# RPi_Carrier.net
KiCad netlist of a schematic drawn in Altium Designer
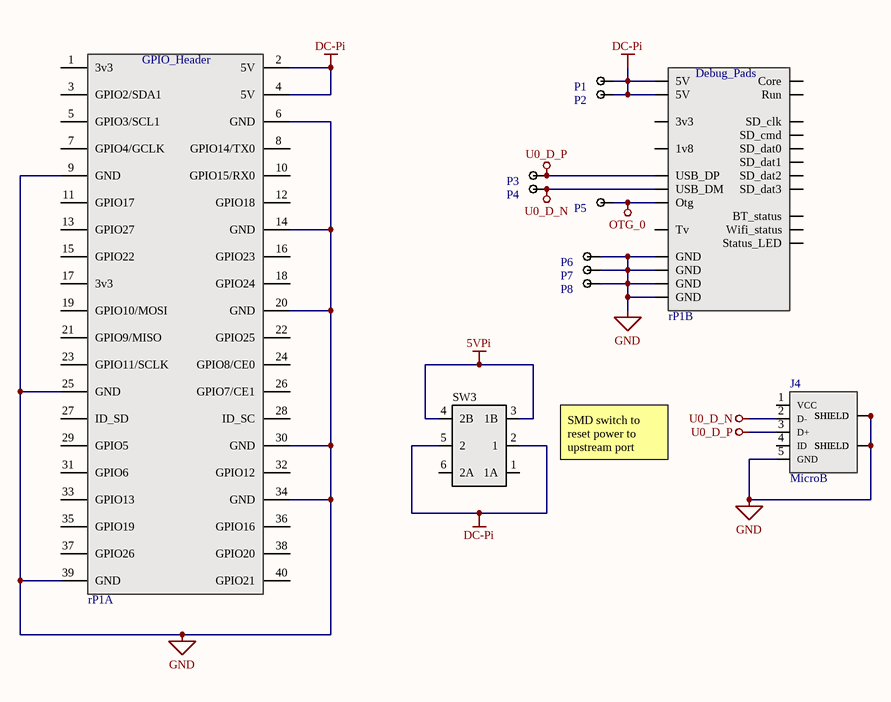
[diagram p0: RPi_Carrier.SchDoc]

(export (version "E")
  (design (tool "Eeschema 10.0.6"))
  (components
    (comp (ref "J4")
      (value "MicroB")
      (footprint "10118194-0001LF")
      (description "Micro USB, Input Output Connectors, B TYPE RECEPTACLE with flange")
      (fields (field (name "MF") "Amphenol ICC") (field (name "MP") "10118194-0001LF"))
      (libsource (lib "Connectors") (part "10118194-0001LF"))
    )
    (comp (ref "P1")
      (value "MillMax Pogo")
      (footprint "0914-1-15-20-77-14-11-0")
      (description "MillMax Pogo Pins/Probes")
      (libsource (lib "Connectors") (part "GenericPogo"))
    )
    (comp (ref "P2")
      (value "MillMax Pogo")
      (footprint "0914-1-15-20-77-14-11-0")
      (description "MillMax Pogo Pins/Probes")
      (libsource (lib "Connectors") (part "GenericPogo"))
    )
    (comp (ref "P3")
      (value "MillMax Pogo")
      (footprint "0914-1-15-20-77-14-11-0")
      (description "MillMax Pogo Pins/Probes")
      (libsource (lib "Connectors") (part "GenericPogo"))
    )
    (comp (ref "P4")
      (value "MillMax Pogo")
      (footprint "0914-1-15-20-77-14-11-0")
      (description "MillMax Pogo Pins/Probes")
      (libsource (lib "Connectors") (part "GenericPogo"))
    )
    (comp (ref "P5")
      (value "MillMax Pogo")
      (footprint "0914-1-15-20-77-14-11-0")
      (description "MillMax Pogo Pins/Probes")
      (libsource (lib "Connectors") (part "GenericPogo"))
    )
    (comp (ref "P6")
      (value "MillMax Pogo")
      (footprint "0914-1-15-20-77-14-11-0")
      (description "MillMax Pogo Pins/Probes")
      (libsource (lib "Connectors") (part "GenericPogo"))
    )
    (comp (ref "P7")
      (value "MillMax Pogo")
      (footprint "0914-1-15-20-77-14-11-0")
      (description "MillMax Pogo Pins/Probes")
      (libsource (lib "Connectors") (part "GenericPogo"))
    )
    (comp (ref "P8")
      (value "MillMax Pogo")
      (footprint "0914-1-15-20-77-14-11-0")
      (description "MillMax Pogo Pins/Probes")
      (libsource (lib "Connectors") (part "GenericPogo"))
    )
    (comp (ref "rP1")
      (value "rPi Zero Carrier")
      (footprint "rPiZero")
      (description "Raspberry Pi Zero/W/2W\r\nHeader, debug-pads, & mounting")
      (libsource (lib "Misc ICs") (part "RP-Zero"))
    )
    (comp (ref "SW3")
      (value "~")
      (footprint "SMD-DPDT-SW")
      (description "Brick nogging DPDT Black SMD Slide Switch")
      (libsource (lib "Switches") (part "MS-22D17-G2"))
    )
  )
  (nets
    (net (code "1") (name "5VPi") (class "Default")
      (node (ref "SW3") (pin "3") (pinfunction "1B_3") (pintype "passive"))
      (node (ref "SW3") (pin "4") (pinfunction "2B_4") (pintype "passive"))
    )
    (net (code "2") (name "DC-Pi") (class "Default")
      (node (ref "P1") (pin "1") (pinfunction "1_1") (pintype "passive"))
      (node (ref "P2") (pin "1") (pinfunction "1_1") (pintype "passive"))
      (node (ref "SW3") (pin "2") (pinfunction "1_2") (pintype "passive"))
      (node (ref "SW3") (pin "5") (pinfunction "2_5") (pintype "passive"))
      (node (ref "rP1") (pin "2") (pinfunction "5V_2") (pintype "passive"))
      (node (ref "rP1") (pin "4") (pinfunction "5V_4") (pintype "passive"))
      (node (ref "rP1") (pin "5V1") (pinfunction "5V_5V1") (pintype "passive"))
      (node (ref "rP1") (pin "5V2") (pinfunction "5V_5V2") (pintype "passive"))
    )
    (net (code "3") (name "GND") (class "Default")
      (node (ref "J4") (pin "5") (pinfunction "GND_5") (pintype "power_in"))
      (node (ref "J4") (pin "SH1") (pinfunction "SHIELD_SH1") (pintype "passive"))
      (node (ref "J4") (pin "SH2") (pinfunction "SHIELD_SH2") (pintype "passive"))
      (node (ref "J4") (pin "SH3") (pinfunction "SHIELD_SH3") (pintype "passive"))
      (node (ref "J4") (pin "SH4") (pinfunction "SHIELD_SH4") (pintype "passive"))
      (node (ref "J4") (pin "SH5") (pinfunction "SHIELD_SH5") (pintype "passive"))
      (node (ref "J4") (pin "SH6") (pinfunction "SHIELD_SH6") (pintype "passive"))
      (node (ref "P6") (pin "1") (pinfunction "1_1") (pintype "passive"))
      (node (ref "P7") (pin "1") (pinfunction "1_1") (pintype "passive"))
      (node (ref "P8") (pin "1") (pinfunction "1_1") (pintype "passive"))
      (node (ref "rP1") (pin "14") (pinfunction "GND_14") (pintype "passive"))
      (node (ref "rP1") (pin "20") (pinfunction "GND_20") (pintype "passive"))
      (node (ref "rP1") (pin "25") (pinfunction "GND_25") (pintype "passive"))
      (node (ref "rP1") (pin "30") (pinfunction "GND_30") (pintype "passive"))
      (node (ref "rP1") (pin "34") (pinfunction "GND_34") (pintype "passive"))
      (node (ref "rP1") (pin "39") (pinfunction "GND_39") (pintype "passive"))
      (node (ref "rP1") (pin "6") (pinfunction "GND_6") (pintype "passive"))
      (node (ref "rP1") (pin "9") (pinfunction "GND_9") (pintype "passive"))
      (node (ref "rP1") (pin "G1") (pinfunction "GND_G1") (pintype "passive"))
      (node (ref "rP1") (pin "G2") (pinfunction "GND_G2") (pintype "passive"))
      (node (ref "rP1") (pin "G3") (pinfunction "GND_G3") (pintype "passive"))
      (node (ref "rP1") (pin "G4") (pinfunction "GND_G4") (pintype "passive"))
    )
    (net (code "4") (name "OTG_0") (class "Default")
      (node (ref "P5") (pin "1") (pinfunction "1_1") (pintype "passive"))
      (node (ref "rP1") (pin "OTG") (pinfunction "Otg_OTG") (pintype "passive"))
    )
    (net (code "5") (name "U0_D_N") (class "Default")
      (node (ref "J4") (pin "2") (pinfunction "D-_2") (pintype "bidirectional"))
      (node (ref "P4") (pin "1") (pinfunction "1_1") (pintype "passive"))
      (node (ref "rP1") (pin "USB_DM") (pinfunction "USB_DM_USB_DM") (pintype "passive"))
    )
    (net (code "6") (name "U0_D_P") (class "Default")
      (node (ref "J4") (pin "3") (pinfunction "D+_3") (pintype "bidirectional"))
      (node (ref "P3") (pin "1") (pinfunction "1_1") (pintype "passive"))
      (node (ref "rP1") (pin "USB_DP") (pinfunction "USB_DP_USB_DP") (pintype "passive"))
    )
    (net (code "7") (name "unconnected-(J4-ID-Pad4)") (class "Default")
      (node (ref "J4") (pin "4") (pinfunction "ID_4") (pintype "bidirectional"))
    )
    (net (code "8") (name "unconnected-(J4-VCC-Pad1)") (class "Default")
      (node (ref "J4") (pin "1") (pinfunction "VCC_1") (pintype "power_in"))
    )
    (net (code "9") (name "unconnected-(SW3-1A-Pad1)") (class "Default")
      (node (ref "SW3") (pin "1") (pinfunction "1A_1") (pintype "passive"))
    )
    (net (code "10") (name "unconnected-(SW3-2A-Pad6)") (class "Default")
      (node (ref "SW3") (pin "6") (pinfunction "2A_6") (pintype "passive"))
    )
    (net (code "11") (name "unconnected-(rP1A-3v3-Pad1)") (class "Default")
      (node (ref "rP1") (pin "1") (pinfunction "3v3_1") (pintype "passive"))
    )
    (net (code "12") (name "unconnected-(rP1A-3v3-Pad17)") (class "Default")
      (node (ref "rP1") (pin "17") (pinfunction "3v3_17") (pintype "passive"))
    )
    (net (code "13") (name "unconnected-(rP1A-GPIO2{slash}SDA1-Pad3)") (class "Default")
      (node (ref "rP1") (pin "3") (pinfunction "GPIO2/SDA1_3") (pintype "passive"))
    )
    (net (code "14") (name "unconnected-(rP1A-GPIO3{slash}SCL1-Pad5)") (class "Default")
      (node (ref "rP1") (pin "5") (pinfunction "GPIO3/SCL1_5") (pintype "passive"))
    )
    (net (code "15") (name "unconnected-(rP1A-GPIO4{slash}GCLK-Pad7)") (class "Default")
      (node (ref "rP1") (pin "7") (pinfunction "GPIO4/GCLK_7") (pintype "passive"))
    )
    (net (code "16") (name "unconnected-(rP1A-GPIO5-Pad29)") (class "Default")
      (node (ref "rP1") (pin "29") (pinfunction "GPIO5_29") (pintype "passive"))
    )
    (net (code "17") (name "unconnected-(rP1A-GPIO6-Pad31)") (class "Default")
      (node (ref "rP1") (pin "31") (pinfunction "GPIO6_31") (pintype "passive"))
    )
    (net (code "18") (name "unconnected-(rP1A-GPIO7{slash}CE1-Pad26)") (class "Default")
      (node (ref "rP1") (pin "26") (pinfunction "GPIO7/CE1_26") (pintype "passive"))
    )
    (net (code "19") (name "unconnected-(rP1A-GPIO8{slash}CE0-Pad24)") (class "Default")
      (node (ref "rP1") (pin "24") (pinfunction "GPIO8/CE0_24") (pintype "passive"))
    )
    (net (code "20") (name "unconnected-(rP1A-GPIO9{slash}MISO-Pad21)") (class "Default")
      (node (ref "rP1") (pin "21") (pinfunction "GPIO9/MISO_21") (pintype "passive"))
    )
    (net (code "21") (name "unconnected-(rP1A-GPIO10{slash}MOSI-Pad19)") (class "Default")
      (node (ref "rP1") (pin "19") (pinfunction "GPIO10/MOSI_19") (pintype "passive"))
    )
    (net (code "22") (name "unconnected-(rP1A-GPIO11{slash}SCLK-Pad23)") (class "Default")
      (node (ref "rP1") (pin "23") (pinfunction "GPIO11/SCLK_23") (pintype "passive"))
    )
    (net (code "23") (name "unconnected-(rP1A-GPIO12-Pad32)") (class "Default")
      (node (ref "rP1") (pin "32") (pinfunction "GPIO12_32") (pintype "passive"))
    )
    (net (code "24") (name "unconnected-(rP1A-GPIO13-Pad33)") (class "Default")
      (node (ref "rP1") (pin "33") (pinfunction "GPIO13_33") (pintype "passive"))
    )
    (net (code "25") (name "unconnected-(rP1A-GPIO14{slash}TX0-Pad8)") (class "Default")
      (node (ref "rP1") (pin "8") (pinfunction "GPIO14/TX0_8") (pintype "passive"))
    )
    (net (code "26") (name "unconnected-(rP1A-GPIO15{slash}RX0-Pad10)") (class "Default")
      (node (ref "rP1") (pin "10") (pinfunction "GPIO15/RX0_10") (pintype "passive"))
    )
    (net (code "27") (name "unconnected-(rP1A-GPIO16-Pad36)") (class "Default")
      (node (ref "rP1") (pin "36") (pinfunction "GPIO16_36") (pintype "passive"))
    )
    (net (code "28") (name "unconnected-(rP1A-GPIO17-Pad11)") (class "Default")
      (node (ref "rP1") (pin "11") (pinfunction "GPIO17_11") (pintype "passive"))
    )
    (net (code "29") (name "unconnected-(rP1A-GPIO18-Pad12)") (class "Default")
      (node (ref "rP1") (pin "12") (pinfunction "GPIO18_12") (pintype "passive"))
    )
    (net (code "30") (name "unconnected-(rP1A-GPIO19-Pad35)") (class "Default")
      (node (ref "rP1") (pin "35") (pinfunction "GPIO19_35") (pintype "passive"))
    )
    (net (code "31") (name "unconnected-(rP1A-GPIO20-Pad38)") (class "Default")
      (node (ref "rP1") (pin "38") (pinfunction "GPIO20_38") (pintype "passive"))
    )
    (net (code "32") (name "unconnected-(rP1A-GPIO21-Pad40)") (class "Default")
      (node (ref "rP1") (pin "40") (pinfunction "GPIO21_40") (pintype "passive"))
    )
    (net (code "33") (name "unconnected-(rP1A-GPIO22-Pad15)") (class "Default")
      (node (ref "rP1") (pin "15") (pinfunction "GPIO22_15") (pintype "passive"))
    )
    (net (code "34") (name "unconnected-(rP1A-GPIO23-Pad16)") (class "Default")
      (node (ref "rP1") (pin "16") (pinfunction "GPIO23_16") (pintype "passive"))
    )
    (net (code "35") (name "unconnected-(rP1A-GPIO24-Pad18)") (class "Default")
      (node (ref "rP1") (pin "18") (pinfunction "GPIO24_18") (pintype "passive"))
    )
    (net (code "36") (name "unconnected-(rP1A-GPIO25-Pad22)") (class "Default")
      (node (ref "rP1") (pin "22") (pinfunction "GPIO25_22") (pintype "passive"))
    )
    (net (code "37") (name "unconnected-(rP1A-GPIO26-Pad37)") (class "Default")
      (node (ref "rP1") (pin "37") (pinfunction "GPIO26_37") (pintype "passive"))
    )
    (net (code "38") (name "unconnected-(rP1A-GPIO27-Pad13)") (class "Default")
      (node (ref "rP1") (pin "13") (pinfunction "GPIO27_13") (pintype "passive"))
    )
    (net (code "39") (name "unconnected-(rP1A-ID_SC-Pad28)") (class "Default")
      (node (ref "rP1") (pin "28") (pinfunction "ID_SC_28") (pintype "passive"))
    )
    (net (code "40") (name "unconnected-(rP1A-ID_SD-Pad27)") (class "Default")
      (node (ref "rP1") (pin "27") (pinfunction "ID_SD_27") (pintype "passive"))
    )
    (net (code "41") (name "unconnected-(rP1B-1v8-Pad1V8)") (class "Default")
      (node (ref "rP1") (pin "1V8") (pinfunction "1v8_1V8") (pintype "passive"))
    )
    (net (code "42") (name "unconnected-(rP1B-3v3-Pad3V3)") (class "Default")
      (node (ref "rP1") (pin "3V3") (pinfunction "3v3_3V3") (pintype "passive"))
    )
    (net (code "43") (name "unconnected-(rP1B-BT_status-PadBT_ON)") (class "Default")
      (node (ref "rP1") (pin "BT_ON") (pinfunction "BT_status_BT_ON") (pintype "passive"))
    )
    (net (code "44") (name "unconnected-(rP1B-Core-PadCORE)") (class "Default")
      (node (ref "rP1") (pin "CORE") (pinfunction "Core_CORE") (pintype "passive"))
    )
    (net (code "45") (name "unconnected-(rP1B-Run-PadRUN)") (class "Default")
      (node (ref "rP1") (pin "RUN") (pinfunction "Run_RUN") (pintype "passive"))
    )
    (net (code "46") (name "unconnected-(rP1B-SD_clk-PadSD_CLK)") (class "Default")
      (node (ref "rP1") (pin "SD_CLK") (pinfunction "SD_clk_SD_CLK") (pintype "passive"))
    )
    (net (code "47") (name "unconnected-(rP1B-SD_cmd-PadSD_CMD)") (class "Default")
      (node (ref "rP1") (pin "SD_CMD") (pinfunction "SD_cmd_SD_CMD") (pintype "passive"))
    )
    (net (code "48") (name "unconnected-(rP1B-SD_dat0-PadSD_DAT0)") (class "Default")
      (node (ref "rP1") (pin "SD_DAT0") (pinfunction "SD_dat0_SD_DAT0") (pintype "passive"))
    )
    (net (code "49") (name "unconnected-(rP1B-SD_dat1-PadSD_DAT1)") (class "Default")
      (node (ref "rP1") (pin "SD_DAT1") (pinfunction "SD_dat1_SD_DAT1") (pintype "passive"))
    )
    (net (code "50") (name "unconnected-(rP1B-SD_dat2-PadSD_DAT2)") (class "Default")
      (node (ref "rP1") (pin "SD_DAT2") (pinfunction "SD_dat2_SD_DAT2") (pintype "passive"))
    )
    (net (code "51") (name "unconnected-(rP1B-SD_dat3-PadSD_DAT3)") (class "Default")
      (node (ref "rP1") (pin "SD_DAT3") (pinfunction "SD_dat3_SD_DAT3") (pintype "passive"))
    )
    (net (code "52") (name "unconnected-(rP1B-Status_LED-PadSTATUS)") (class "Default")
      (node (ref "rP1") (pin "STATUS") (pinfunction "Status_LED_STATUS") (pintype "passive"))
    )
    (net (code "53") (name "unconnected-(rP1B-Tv-PadTV)") (class "Default")
      (node (ref "rP1") (pin "TV") (pinfunction "Tv_TV") (pintype "passive"))
    )
    (net (code "54") (name "unconnected-(rP1B-Wifi_status-PadWL_ON)") (class "Default")
      (node (ref "rP1") (pin "WL_ON") (pinfunction "Wifi_status_WL_ON") (pintype "passive"))
    )
  )
)
